# esparducam-v2.net
KiCad netlist of a schematic drawn in EAGLE
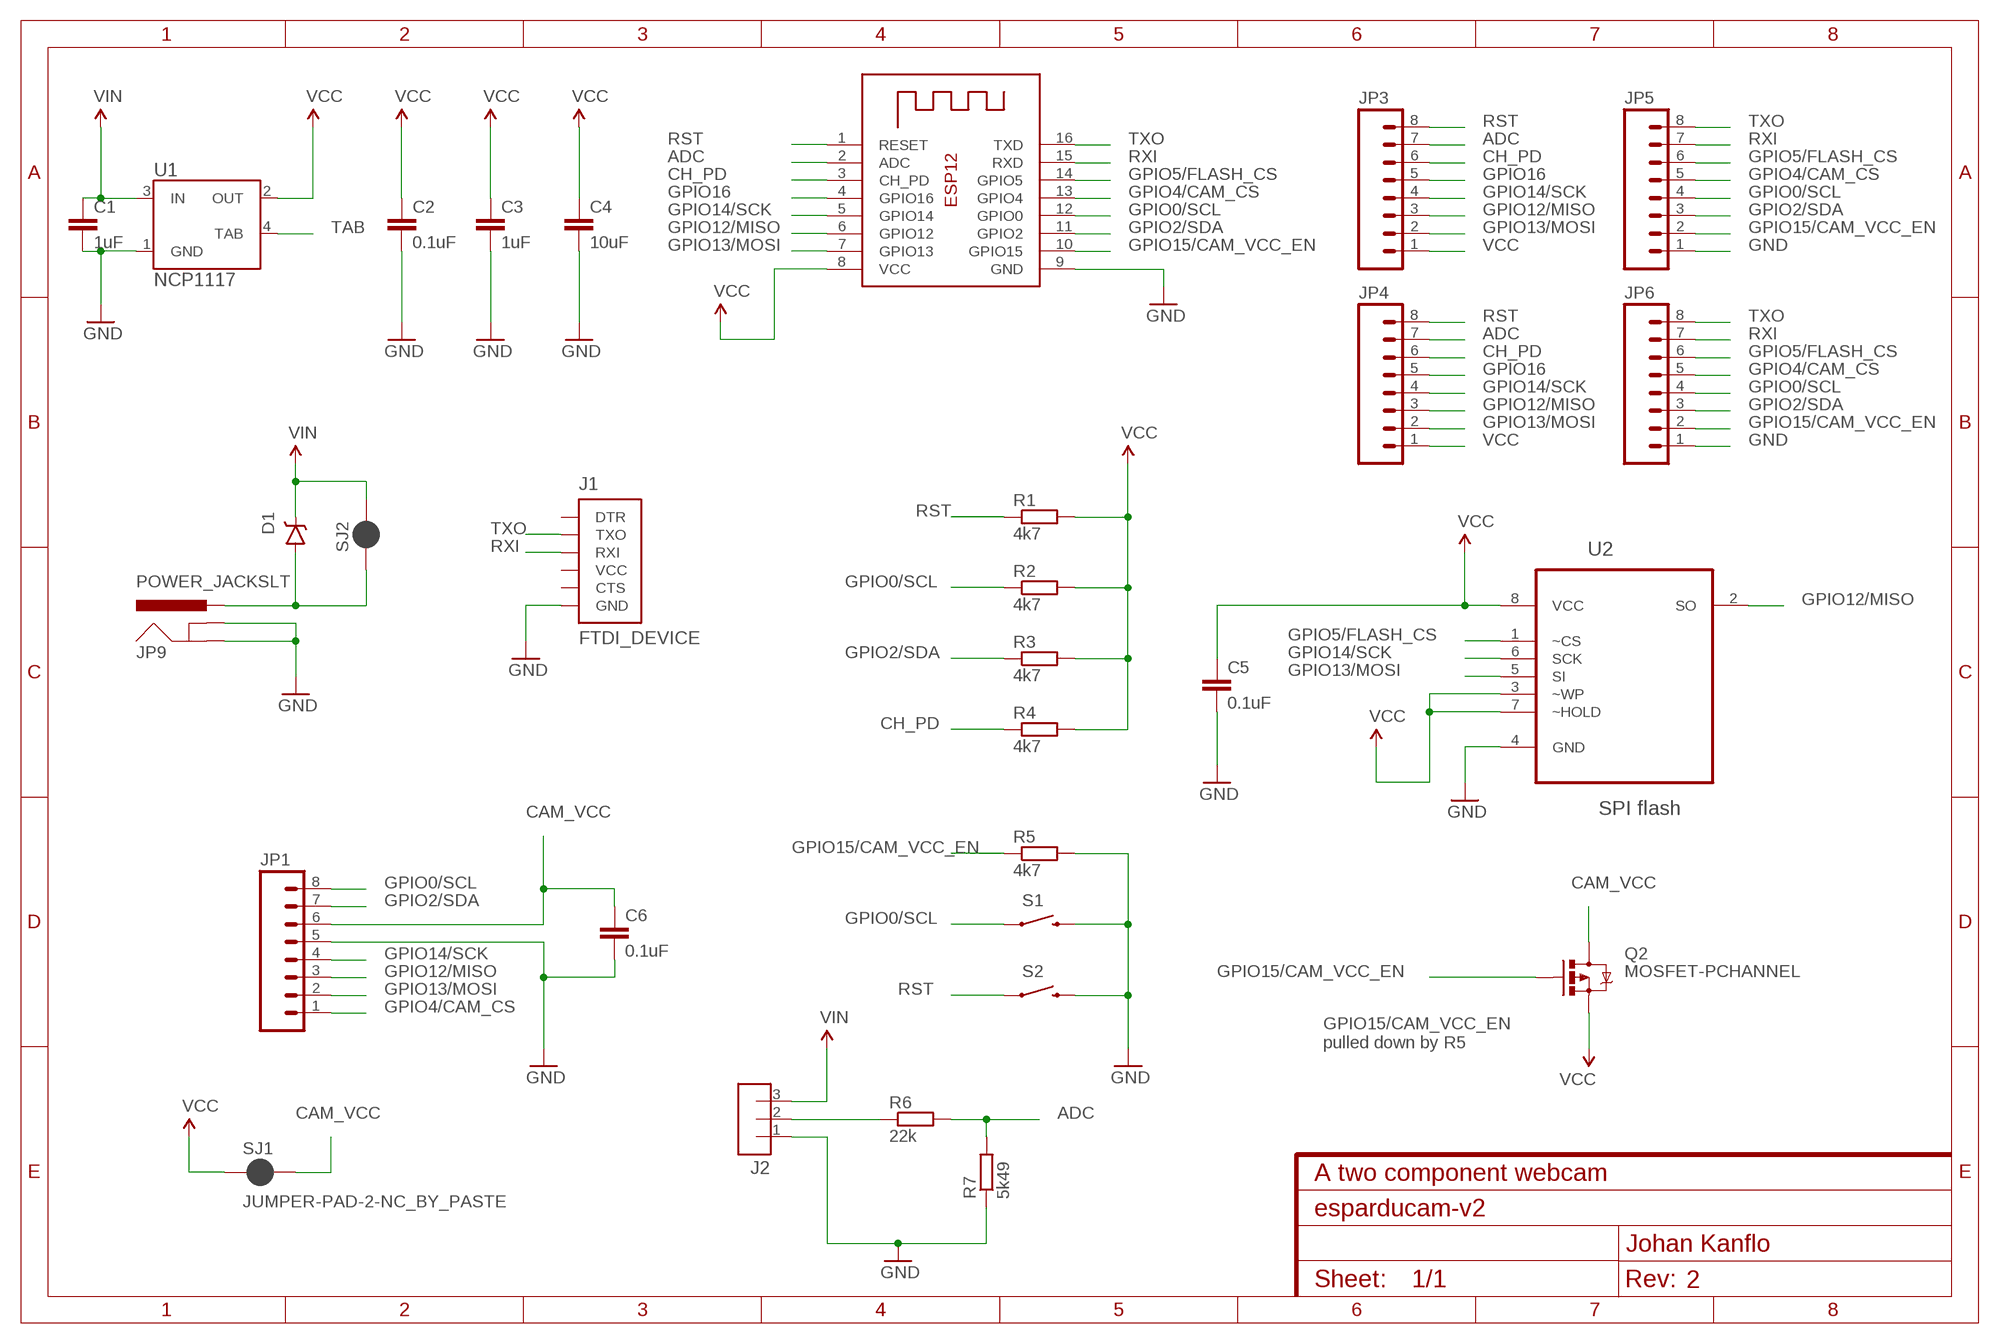
[diagram p0: schematic, sheet 1]

(export (version "E")
  (design (tool "Eeschema 10.0.6"))
  (components
    (comp (ref "C1")
      (value "1uF")
      (footprint "eagle-import:0603-CAP")
      (libsource (lib "eagle-import") (part "CAP0603-CAP"))
    )
    (comp (ref "C2")
      (value "0.1uF")
      (footprint "eagle-import:0603-CAP")
      (libsource (lib "eagle-import") (part "CAP0603-CAP"))
    )
    (comp (ref "C3")
      (value "1uF")
      (footprint "eagle-import:0603-CAP")
      (libsource (lib "eagle-import") (part "CAP0603-CAP"))
    )
    (comp (ref "C4")
      (value "10uF")
      (footprint "eagle-import:0603-CAP")
      (libsource (lib "eagle-import") (part "CAP0603-CAP"))
    )
    (comp (ref "C5")
      (value "0.1uF")
      (footprint "eagle-import:0603-CAP")
      (libsource (lib "eagle-import") (part "CAP0603-CAP"))
    )
    (comp (ref "C6")
      (value "0.1uF")
      (footprint "eagle-import:0603-CAP")
      (libsource (lib "eagle-import") (part "CAP0603-CAP"))
    )
    (comp (ref "D1")
      (value "DIODE-SCHOTTKYSOD-123FL")
      (footprint "eagle-import:SOD-123FL")
      (libsource (lib "eagle-import") (part "DIODE-SCHOTTKYSOD-123FL"))
    )
    (comp (ref "J1")
      (value "FTDI_DEVICE")
      (footprint "eagle-import:FTDI")
      (libsource (lib "eagle-import") (part "FTDI_DEVICE"))
    )
    (comp (ref "J2")
      (value "JST_ZH_3PIN")
      (footprint "eagle-import:JST_ZH_3PIN")
      (libsource (lib "eagle-import") (part "JST_ZH_3PIN"))
    )
    (comp (ref "JP1")
      (value "M08")
      (footprint "eagle-import:1X08_ROUND")
      (libsource (lib "eagle-import") (part "M08"))
    )
    (comp (ref "JP3")
      (value "M08")
      (footprint "eagle-import:1X08_ROUND")
      (libsource (lib "eagle-import") (part "M08"))
    )
    (comp (ref "JP4")
      (value "M08")
      (footprint "eagle-import:1X08_ROUND")
      (libsource (lib "eagle-import") (part "M08"))
    )
    (comp (ref "JP5")
      (value "M08")
      (footprint "eagle-import:1X08_ROUND")
      (libsource (lib "eagle-import") (part "M08"))
    )
    (comp (ref "JP6")
      (value "M08")
      (footprint "eagle-import:1X08_ROUND")
      (libsource (lib "eagle-import") (part "M08"))
    )
    (comp (ref "JP9")
      (value "POWER_JACKSLT")
      (footprint "eagle-import:POWER_JACK_SLOT")
      (libsource (lib "eagle-import") (part "POWER_JACKSLT"))
    )
    (comp (ref "Q2")
      (value "MOSFET-PCHANNEL")
      (footprint "eagle-import:SOT23-3")
      (libsource (lib "eagle-import") (part "MOSFET-PCHANNEL"))
    )
    (comp (ref "R1")
      (value "4k7")
      (footprint "eagle-import:R0603")
      (libsource (lib "eagle-import") (part "R-EU_R0603"))
    )
    (comp (ref "R2")
      (value "4k7")
      (footprint "eagle-import:R0603")
      (libsource (lib "eagle-import") (part "R-EU_R0603"))
    )
    (comp (ref "R3")
      (value "4k7")
      (footprint "eagle-import:R0603")
      (libsource (lib "eagle-import") (part "R-EU_R0603"))
    )
    (comp (ref "R4")
      (value "4k7")
      (footprint "eagle-import:R0603")
      (libsource (lib "eagle-import") (part "R-EU_R0603"))
    )
    (comp (ref "R5")
      (value "4k7")
      (footprint "eagle-import:R0603")
      (libsource (lib "eagle-import") (part "R-EU_R0603"))
    )
    (comp (ref "R6")
      (value "22k")
      (footprint "eagle-import:R0603")
      (libsource (lib "eagle-import") (part "R-EU_R0603"))
    )
    (comp (ref "R7")
      (value "5k49")
      (footprint "eagle-import:R0603")
      (libsource (lib "eagle-import") (part "R-EU_R0603"))
    )
    (comp (ref "S1")
      (value "SWITCH-MOMENTARY-2SMD-1101NE")
      (footprint "eagle-import:TACTILE-SWITCH-1101NE")
      (libsource (lib "eagle-import") (part "SWITCH-MOMENTARY-2SMD-1101NE"))
    )
    (comp (ref "S2")
      (value "SWITCH-MOMENTARY-2SMD-1101NE")
      (footprint "eagle-import:TACTILE-SWITCH-1101NE")
      (libsource (lib "eagle-import") (part "SWITCH-MOMENTARY-2SMD-1101NE"))
    )
    (comp (ref "SJ1")
      (value "JUMPER-PAD-2-NC_BY_PASTE")
      (footprint "eagle-import:PAD-JUMPER-2-NC_BY_PASTE_YES_SILK")
      (libsource (lib "eagle-import") (part "JUMPER-PAD-2-NC_BY_PASTE"))
    )
    (comp (ref "SJ2")
      (value "JUMPER-PAD-2-NC_BY_PASTE")
      (footprint "eagle-import:PAD-JUMPER-2-NC_BY_PASTE_YES_SILK")
      (libsource (lib "eagle-import") (part "JUMPER-PAD-2-NC_BY_PASTE"))
    )
    (comp (ref "U1")
      (value "NCP1117")
      (footprint "eagle-import:SOT223")
      (libsource (lib "eagle-import") (part "NCP1117"))
    )
    (comp (ref "U2")
      (value "SPI flash")
      (footprint "eagle-import:SOIC127P600X175-8N")
      (fields (field (name "MPN") "AT25DF021-SSH-B"))
      (libsource (lib "eagle-import") (part "AT25DF021-SSH-B"))
    )
    (comp (ref "X1")
      (value "ESP-12")
      (footprint "eagle-import:ESP-12")
      (libsource (lib "eagle-import") (part "ESP-12"))
    )
  )
  (nets
    (net (code "1") (name "/ADC") (class "Default")
      (node (ref "JP3") (pin "7") (pinfunction "7_7") (pintype "passive"))
      (node (ref "JP4") (pin "7") (pinfunction "7_7") (pintype "passive"))
      (node (ref "R6") (pin "2") (pinfunction "2_2") (pintype "passive"))
      (node (ref "R7") (pin "2") (pinfunction "2_2") (pintype "passive"))
      (node (ref "X1") (pin "2") (pinfunction "ADC_2") (pintype "passive"))
    )
    (net (code "2") (name "/CAM_VCC") (class "Default")
      (node (ref "C6") (pin "1") (pinfunction "1_1") (pintype "passive"))
      (node (ref "JP1") (pin "6") (pinfunction "6_6") (pintype "passive"))
      (node (ref "Q2") (pin "3") (pinfunction "D_3") (pintype "passive"))
      (node (ref "SJ1") (pin "2") (pinfunction "2_2") (pintype "passive"))
    )
    (net (code "3") (name "/CH_PD") (class "Default")
      (node (ref "JP3") (pin "6") (pinfunction "6_6") (pintype "passive"))
      (node (ref "JP4") (pin "6") (pinfunction "6_6") (pintype "passive"))
      (node (ref "R4") (pin "1") (pinfunction "1_1") (pintype "passive"))
      (node (ref "X1") (pin "3") (pinfunction "CH_PD_3") (pintype "input"))
    )
    (net (code "4") (name "/GPIO0{slash}SCL") (class "Default")
      (node (ref "JP1") (pin "8") (pinfunction "8_8") (pintype "passive"))
      (node (ref "JP5") (pin "4") (pinfunction "4_4") (pintype "passive"))
      (node (ref "JP6") (pin "4") (pinfunction "4_4") (pintype "passive"))
      (node (ref "R2") (pin "1") (pinfunction "1_1") (pintype "passive"))
      (node (ref "S1") (pin "1") (pinfunction "1_1") (pintype "passive"))
      (node (ref "X1") (pin "12") (pinfunction "GPIO0_12") (pintype "bidirectional"))
    )
    (net (code "5") (name "/GPIO2{slash}SDA") (class "Default")
      (node (ref "JP1") (pin "7") (pinfunction "7_7") (pintype "passive"))
      (node (ref "JP5") (pin "3") (pinfunction "3_3") (pintype "passive"))
      (node (ref "JP6") (pin "3") (pinfunction "3_3") (pintype "passive"))
      (node (ref "R3") (pin "1") (pinfunction "1_1") (pintype "passive"))
      (node (ref "X1") (pin "11") (pinfunction "GPIO2_11") (pintype "bidirectional"))
    )
    (net (code "6") (name "/GPIO4{slash}CAM_CS") (class "Default")
      (node (ref "JP1") (pin "1") (pinfunction "1_1") (pintype "passive"))
      (node (ref "JP5") (pin "5") (pinfunction "5_5") (pintype "passive"))
      (node (ref "JP6") (pin "5") (pinfunction "5_5") (pintype "passive"))
      (node (ref "X1") (pin "13") (pinfunction "GPIO4_13") (pintype "bidirectional"))
    )
    (net (code "7") (name "/GPIO5{slash}FLASH_CS") (class "Default")
      (node (ref "JP5") (pin "6") (pinfunction "6_6") (pintype "passive"))
      (node (ref "JP6") (pin "6") (pinfunction "6_6") (pintype "passive"))
      (node (ref "U2") (pin "1") (pinfunction "~{CS}_1") (pintype "input"))
      (node (ref "X1") (pin "14") (pinfunction "GPIO5_14") (pintype "bidirectional"))
    )
    (net (code "8") (name "/GPIO12{slash}MISO") (class "Default")
      (node (ref "JP1") (pin "3") (pinfunction "3_3") (pintype "passive"))
      (node (ref "JP3") (pin "3") (pinfunction "3_3") (pintype "passive"))
      (node (ref "JP4") (pin "3") (pinfunction "3_3") (pintype "passive"))
      (node (ref "U2") (pin "2") (pinfunction "SO_2") (pintype "output"))
      (node (ref "X1") (pin "6") (pinfunction "GPIO12_6") (pintype "bidirectional"))
    )
    (net (code "9") (name "/GPIO13{slash}MOSI") (class "Default")
      (node (ref "JP1") (pin "2") (pinfunction "2_2") (pintype "passive"))
      (node (ref "JP3") (pin "2") (pinfunction "2_2") (pintype "passive"))
      (node (ref "JP4") (pin "2") (pinfunction "2_2") (pintype "passive"))
      (node (ref "U2") (pin "5") (pinfunction "SI_5") (pintype "input"))
      (node (ref "X1") (pin "7") (pinfunction "GPIO13_7") (pintype "bidirectional"))
    )
    (net (code "10") (name "/GPIO14{slash}SCK") (class "Default")
      (node (ref "JP1") (pin "4") (pinfunction "4_4") (pintype "passive"))
      (node (ref "JP3") (pin "4") (pinfunction "4_4") (pintype "passive"))
      (node (ref "JP4") (pin "4") (pinfunction "4_4") (pintype "passive"))
      (node (ref "U2") (pin "6") (pinfunction "SCK_6") (pintype "input"))
      (node (ref "X1") (pin "5") (pinfunction "GPIO14_5") (pintype "bidirectional"))
    )
    (net (code "11") (name "/GPIO15{slash}CAM_VCC_EN") (class "Default")
      (node (ref "JP5") (pin "2") (pinfunction "2_2") (pintype "passive"))
      (node (ref "JP6") (pin "2") (pinfunction "2_2") (pintype "passive"))
      (node (ref "Q2") (pin "1") (pinfunction "G_1") (pintype "passive"))
      (node (ref "R5") (pin "1") (pinfunction "1_1") (pintype "passive"))
      (node (ref "X1") (pin "10") (pinfunction "GPIO15_10") (pintype "bidirectional"))
    )
    (net (code "12") (name "/GPIO16") (class "Default")
      (node (ref "JP3") (pin "5") (pinfunction "5_5") (pintype "passive"))
      (node (ref "JP4") (pin "5") (pinfunction "5_5") (pintype "passive"))
      (node (ref "X1") (pin "4") (pinfunction "GPIO16_4") (pintype "bidirectional"))
    )
    (net (code "13") (name "/RST") (class "Default")
      (node (ref "JP3") (pin "8") (pinfunction "8_8") (pintype "passive"))
      (node (ref "JP4") (pin "8") (pinfunction "8_8") (pintype "passive"))
      (node (ref "R1") (pin "1") (pinfunction "1_1") (pintype "passive"))
      (node (ref "S2") (pin "1") (pinfunction "1_1") (pintype "passive"))
      (node (ref "X1") (pin "1") (pinfunction "RESET_1") (pintype "input"))
    )
    (net (code "14") (name "/RXI") (class "Default")
      (node (ref "J1") (pin "RXI") (pinfunction "RXI_RXI") (pintype "input"))
      (node (ref "JP5") (pin "7") (pinfunction "7_7") (pintype "passive"))
      (node (ref "JP6") (pin "7") (pinfunction "7_7") (pintype "passive"))
      (node (ref "X1") (pin "15") (pinfunction "RXD_15") (pintype "input"))
    )
    (net (code "15") (name "/TAB") (class "Default")
      (node (ref "U1") (pin "4") (pinfunction "TAB_4") (pintype "bidirectional"))
    )
    (net (code "16") (name "/TXO") (class "Default")
      (node (ref "J1") (pin "TXO") (pinfunction "TXO_TXO") (pintype "output"))
      (node (ref "JP5") (pin "8") (pinfunction "8_8") (pintype "passive"))
      (node (ref "JP6") (pin "8") (pinfunction "8_8") (pintype "passive"))
      (node (ref "X1") (pin "16") (pinfunction "TXD_16") (pintype "output"))
    )
    (net (code "17") (name "GND") (class "Default")
      (node (ref "C1") (pin "2") (pinfunction "2_2") (pintype "passive"))
      (node (ref "C2") (pin "2") (pinfunction "2_2") (pintype "passive"))
      (node (ref "C3") (pin "2") (pinfunction "2_2") (pintype "passive"))
      (node (ref "C4") (pin "2") (pinfunction "2_2") (pintype "passive"))
      (node (ref "C5") (pin "2") (pinfunction "2_2") (pintype "passive"))
      (node (ref "C6") (pin "2") (pinfunction "2_2") (pintype "passive"))
      (node (ref "J1") (pin "GND") (pinfunction "GND_GND") (pintype "power_in"))
      (node (ref "J2") (pin "1") (pinfunction "1_1") (pintype "bidirectional"))
      (node (ref "JP1") (pin "5") (pinfunction "5_5") (pintype "passive"))
      (node (ref "JP5") (pin "1") (pinfunction "1_1") (pintype "passive"))
      (node (ref "JP6") (pin "1") (pinfunction "1_1") (pintype "passive"))
      (node (ref "JP9") (pin "GND@1") (pinfunction "GNDBREAK_GND@1") (pintype "power_in"))
      (node (ref "JP9") (pin "GND@2") (pinfunction "GND_GND@2") (pintype "power_in"))
      (node (ref "R5") (pin "2") (pinfunction "2_2") (pintype "passive"))
      (node (ref "R7") (pin "1") (pinfunction "1_1") (pintype "passive"))
      (node (ref "S1") (pin "2") (pinfunction "2_2") (pintype "passive"))
      (node (ref "S2") (pin "2") (pinfunction "2_2") (pintype "passive"))
      (node (ref "U1") (pin "1") (pinfunction "GND_1") (pintype "bidirectional"))
      (node (ref "U2") (pin "4") (pinfunction "GND_4") (pintype "passive"))
      (node (ref "X1") (pin "9") (pinfunction "GND_9") (pintype "power_in"))
    )
    (net (code "18") (name "Net-(D1-PadA)") (class "Default")
      (node (ref "D1") (pin "A") (pinfunction "A_A") (pintype "passive"))
      (node (ref "JP9") (pin "PWR") (pinfunction "PWR_PWR") (pintype "power_in"))
      (node (ref "SJ2") (pin "1") (pinfunction "1_1") (pintype "passive"))
    )
    (net (code "19") (name "Net-(J2-Pad2)") (class "Default")
      (node (ref "J2") (pin "2") (pinfunction "2_2") (pintype "bidirectional"))
      (node (ref "R6") (pin "1") (pinfunction "1_1") (pintype "passive"))
    )
    (net (code "20") (name "VCC") (class "Default")
      (node (ref "C2") (pin "1") (pinfunction "1_1") (pintype "passive"))
      (node (ref "C3") (pin "1") (pinfunction "1_1") (pintype "passive"))
      (node (ref "C4") (pin "1") (pinfunction "1_1") (pintype "passive"))
      (node (ref "C5") (pin "1") (pinfunction "1_1") (pintype "passive"))
      (node (ref "JP3") (pin "1") (pinfunction "1_1") (pintype "passive"))
      (node (ref "JP4") (pin "1") (pinfunction "1_1") (pintype "passive"))
      (node (ref "Q2") (pin "2") (pinfunction "S_2") (pintype "passive"))
      (node (ref "R1") (pin "2") (pinfunction "2_2") (pintype "passive"))
      (node (ref "R2") (pin "2") (pinfunction "2_2") (pintype "passive"))
      (node (ref "R3") (pin "2") (pinfunction "2_2") (pintype "passive"))
      (node (ref "R4") (pin "2") (pinfunction "2_2") (pintype "passive"))
      (node (ref "SJ1") (pin "1") (pinfunction "1_1") (pintype "passive"))
      (node (ref "U1") (pin "2") (pinfunction "OUT_2") (pintype "bidirectional"))
      (node (ref "U2") (pin "3") (pinfunction "~{WP}_3") (pintype "input"))
      (node (ref "U2") (pin "7") (pinfunction "~{HOLD}_7") (pintype "input"))
      (node (ref "U2") (pin "8") (pinfunction "VCC_8") (pintype "power_in"))
      (node (ref "X1") (pin "8") (pinfunction "VCC_8") (pintype "power_in"))
    )
    (net (code "21") (name "VIN") (class "Default")
      (node (ref "C1") (pin "1") (pinfunction "1_1") (pintype "passive"))
      (node (ref "D1") (pin "C") (pinfunction "C_C") (pintype "passive"))
      (node (ref "J2") (pin "3") (pinfunction "3_3") (pintype "bidirectional"))
      (node (ref "SJ2") (pin "2") (pinfunction "2_2") (pintype "passive"))
      (node (ref "U1") (pin "3") (pinfunction "IN_3") (pintype "bidirectional"))
    )
    (net (code "22") (name "unconnected-(J1-PadCTS)") (class "Default")
      (node (ref "J1") (pin "CTS") (pinfunction "CTS_CTS") (pintype "input"))
    )
    (net (code "23") (name "unconnected-(J1-PadDTR)") (class "Default")
      (node (ref "J1") (pin "DTR") (pinfunction "DTR_DTR") (pintype "input"))
    )
    (net (code "24") (name "unconnected-(J1-PadVCC)") (class "Default")
      (node (ref "J1") (pin "VCC") (pinfunction "VCC_VCC") (pintype "input"))
    )
  )
)
